# PLD_Sensors_AVR_Interface.net
KiCad netlist of a schematic drawn in Altium Designer
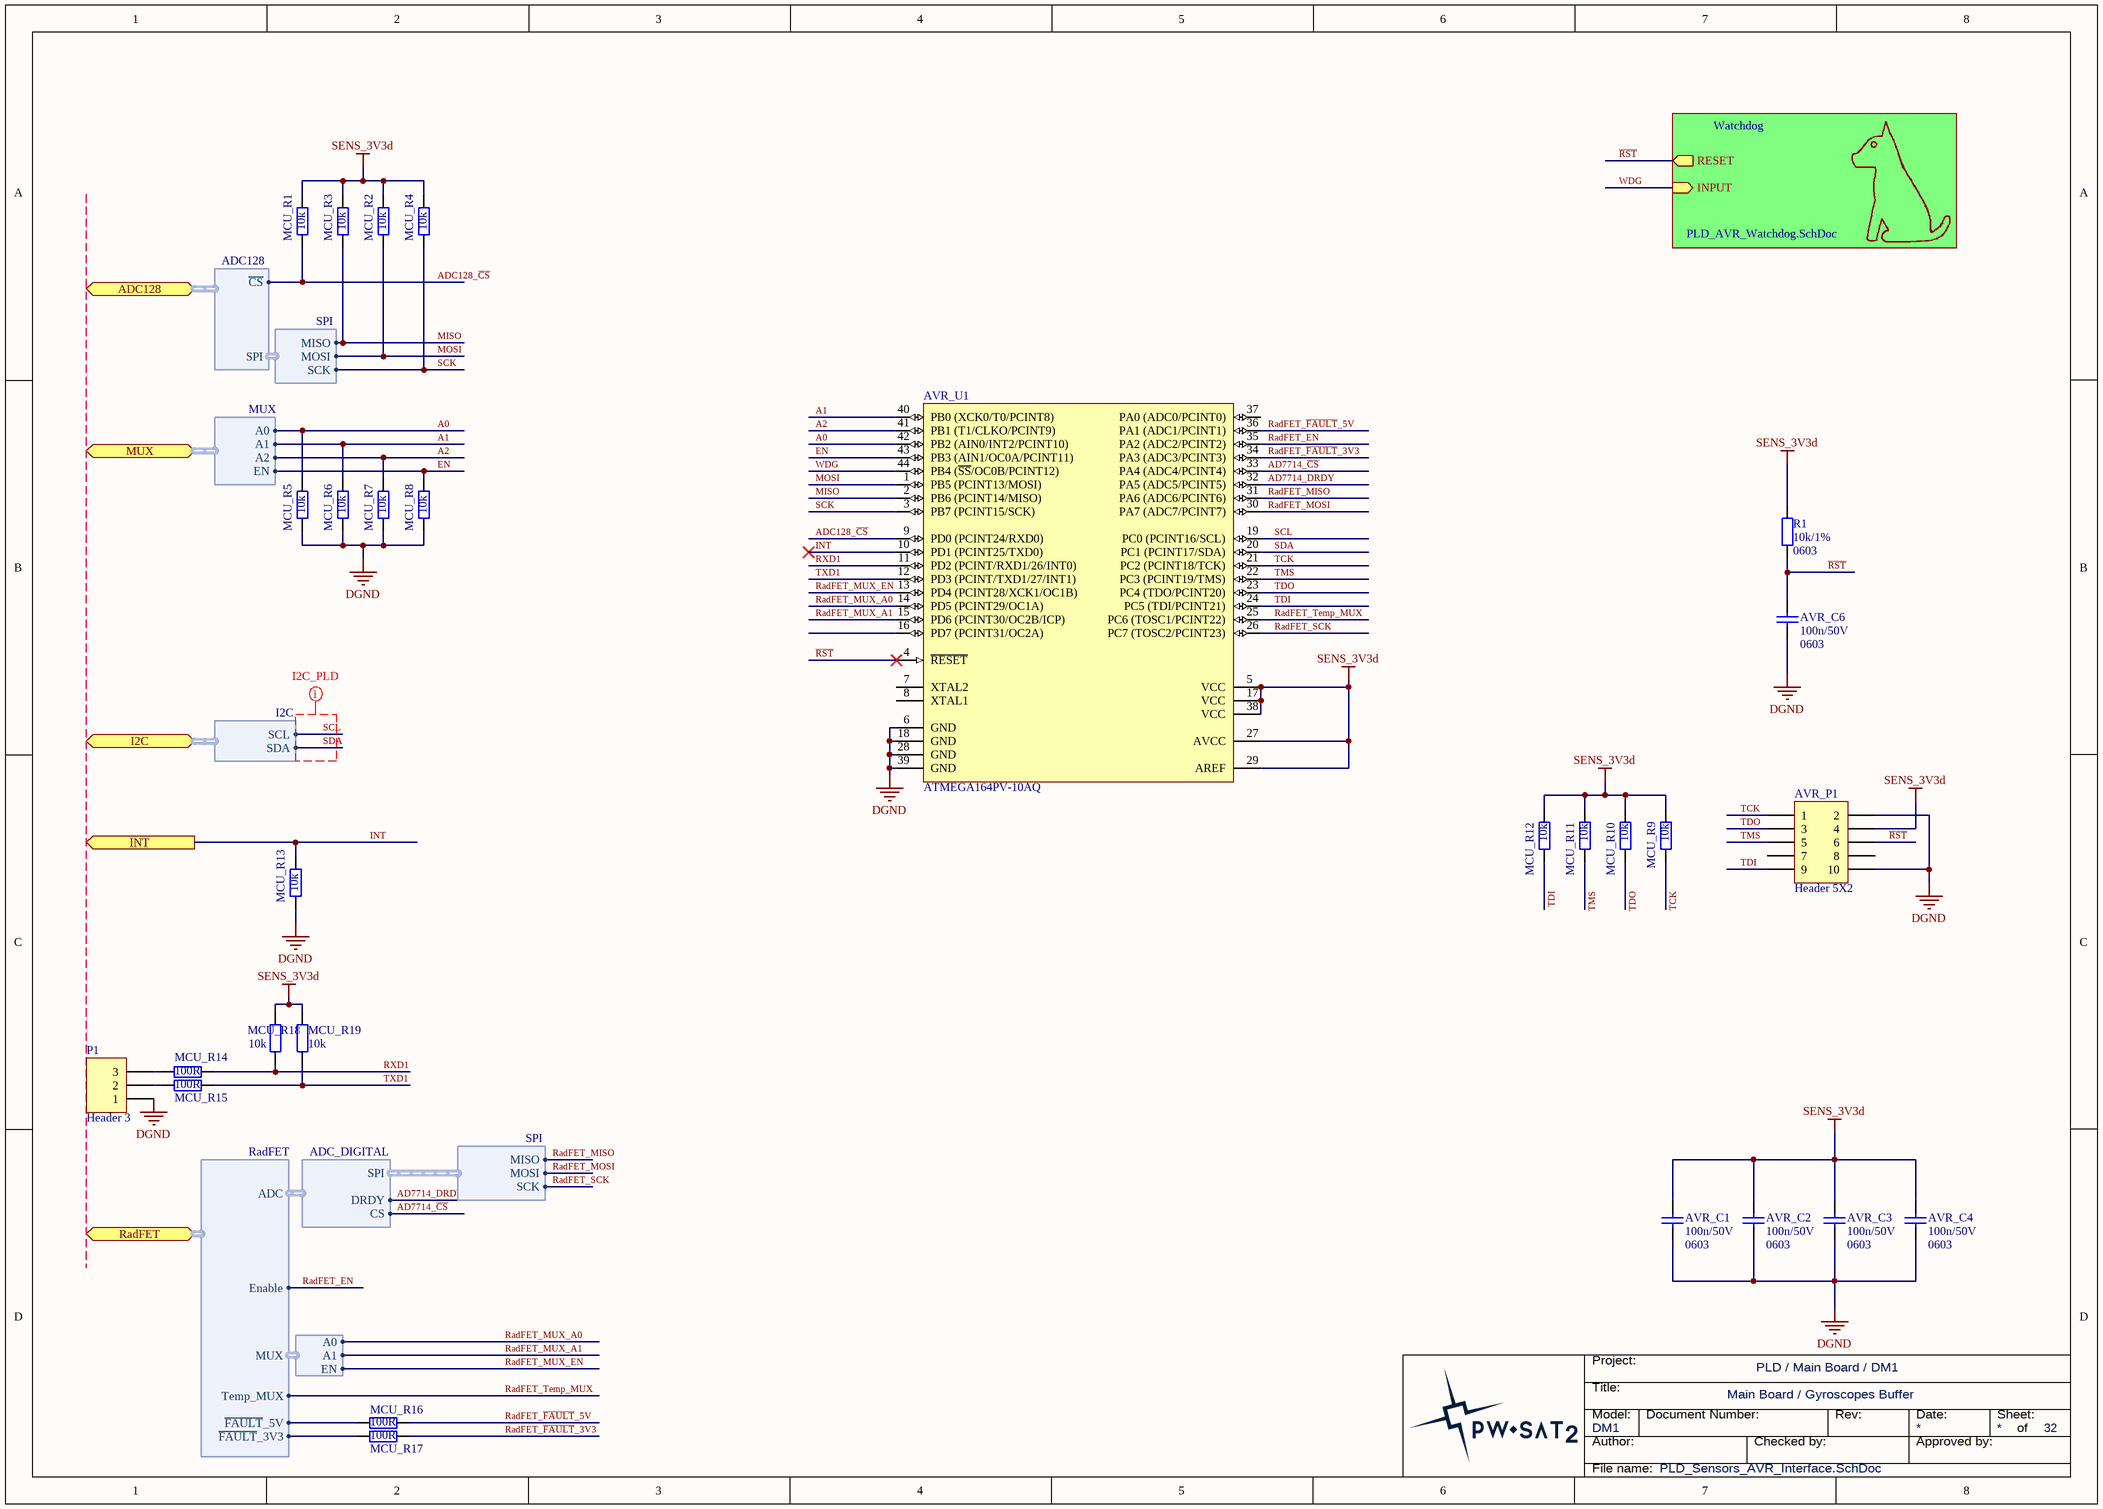
[diagram p0: PLD_Sensors_AVR_Interface.SchDoc]

(export (version "E")
  (design (tool "Eeschema 10.0.6"))
  (components
    (comp (ref "AVR_C1")
      (value "100n/50V")
      (footprint "SMD_Capacitor_0603")
      (description "Ceramic Cap Kemet COTS 100n/50V X7R 0603")
      (fields
        (field (name "MANUFACTURER") "Kemet")
        (field (name "MANUFACTURERPARTNUMBER") "C0603T104K5RALTU")
        (field (name "PACKAGE") "0603")
      )
      (libsource (lib "capacitors") (part "Cer_C0603T104K5RALTU"))
    )
    (comp (ref "AVR_C2")
      (value "100n/50V")
      (footprint "SMD_Capacitor_0603")
      (description "Ceramic Cap Kemet COTS 100n/50V X7R 0603")
      (fields
        (field (name "MANUFACTURER") "Kemet")
        (field (name "MANUFACTURERPARTNUMBER") "C0603T104K5RALTU")
        (field (name "PACKAGE") "0603")
      )
      (libsource (lib "capacitors") (part "Cer_C0603T104K5RALTU"))
    )
    (comp (ref "AVR_C3")
      (value "100n/50V")
      (footprint "SMD_Capacitor_0603")
      (description "Ceramic Cap Kemet COTS 100n/50V X7R 0603")
      (fields
        (field (name "MANUFACTURER") "Kemet")
        (field (name "MANUFACTURERPARTNUMBER") "C0603T104K5RALTU")
        (field (name "PACKAGE") "0603")
      )
      (libsource (lib "capacitors") (part "Cer_C0603T104K5RALTU"))
    )
    (comp (ref "AVR_C4")
      (value "100n/50V")
      (footprint "SMD_Capacitor_0603")
      (description "Ceramic Cap Kemet COTS 100n/50V X7R 0603")
      (fields
        (field (name "MANUFACTURER") "Kemet")
        (field (name "MANUFACTURERPARTNUMBER") "C0603T104K5RALTU")
        (field (name "PACKAGE") "0603")
      )
      (libsource (lib "capacitors") (part "Cer_C0603T104K5RALTU"))
    )
    (comp (ref "AVR_C6")
      (value "100n/50V")
      (footprint "SMD_Capacitor_0603")
      (description "Ceramic Cap Kemet COTS 100n/50V X7R 0603")
      (fields
        (field (name "MANUFACTURER") "Kemet")
        (field (name "MANUFACTURERPARTNUMBER") "C0603T104K5RALTU")
        (field (name "PACKAGE") "0603")
      )
      (libsource (lib "capacitors") (part "Cer_C0603T104K5RALTU"))
    )
    (comp (ref "AVR_P1")
      (value "Header 5X2")
      (footprint "HDR2X5")
      (description "Header, 5-Pin, Dual row")
      (fields (field (name "PUBLISHER") "Altium Limited"))
      (libsource (lib "Miscellaneous Connectors") (part "Header 5X2"))
    )
    (comp (ref "AVR_U1")
      (value "ATMEGA164PV-10AQ")
      (footprint "TQFP-44")
      (description "General-purpose microcontroller")
      (libsource (lib "microcircuits") (part "ATMEGA164PV-10AQ"))
    )
    (comp (ref "MCU_R1")
      (value "10k")
      (footprint "SMD_Resistor_0603")
      (libsource (lib "resistors") (part "Res"))
    )
    (comp (ref "MCU_R2")
      (value "10k")
      (footprint "SMD_Resistor_0603")
      (libsource (lib "resistors") (part "Res"))
    )
    (comp (ref "MCU_R3")
      (value "10k")
      (footprint "SMD_Resistor_0603")
      (libsource (lib "resistors") (part "Res"))
    )
    (comp (ref "MCU_R4")
      (value "10k")
      (footprint "SMD_Resistor_0603")
      (libsource (lib "resistors") (part "Res"))
    )
    (comp (ref "MCU_R5") (value "10k") (footprint "SMD_Resistor_0603") (libsource (lib "") (part "Res_1")))
    (comp (ref "MCU_R6") (value "10k") (footprint "SMD_Resistor_0603") (libsource (lib "") (part "Res_1")))
    (comp (ref "MCU_R7") (value "10k") (footprint "SMD_Resistor_0603") (libsource (lib "") (part "Res_1")))
    (comp (ref "MCU_R8") (value "10k") (footprint "SMD_Resistor_0603") (libsource (lib "") (part "Res_1")))
    (comp (ref "MCU_R9")
      (value "10k")
      (footprint "SMD_Resistor_0603")
      (libsource (lib "resistors") (part "Res"))
    )
    (comp (ref "MCU_R10")
      (value "10k")
      (footprint "SMD_Resistor_0603")
      (libsource (lib "resistors") (part "Res"))
    )
    (comp (ref "MCU_R11")
      (value "10k")
      (footprint "SMD_Resistor_0603")
      (libsource (lib "resistors") (part "Res"))
    )
    (comp (ref "MCU_R12")
      (value "10k")
      (footprint "SMD_Resistor_0603")
      (libsource (lib "resistors") (part "Res"))
    )
    (comp (ref "MCU_R13")
      (value "10k")
      (footprint "SMD_Resistor_0603")
      (libsource (lib "resistors") (part "Res"))
    )
    (comp (ref "MCU_R14") (value "100R") (footprint "SMD_Resistor_0603") (libsource (lib "") (part "Res_2")))
    (comp (ref "MCU_R15") (value "100R") (footprint "SMD_Resistor_0603") (libsource (lib "") (part "Res_2")))
    (comp (ref "MCU_R16") (value "100R") (footprint "SMD_Resistor_0603") (libsource (lib "") (part "Res_2")))
    (comp (ref "MCU_R17") (value "100R") (footprint "SMD_Resistor_0603") (libsource (lib "") (part "Res_2")))
    (comp (ref "MCU_R18")
      (value "10k")
      (footprint "SMD_Resistor_0603")
      (libsource (lib "resistors") (part "Res"))
    )
    (comp (ref "MCU_R19")
      (value "10k")
      (footprint "SMD_Resistor_0603")
      (libsource (lib "resistors") (part "Res"))
    )
    (comp (ref "P1")
      (value "Header 3")
      (footprint "HEADER1X3H Male")
      (description "Header, 3-Pin")
      (fields (field (name "PUBLISHER") "Altium Limited"))
      (libsource (lib "connectors_printed-circuit-board") (part "Header 3"))
    )
    (comp (ref "R1")
      (value "10k/1%")
      (footprint "SMD_Resistor_0603")
      (description "10k/1% Vishay CRCW 0603 Resistor. 100mW, 100ppm, 75V.")
      (fields
        (field (name "MANUFACTURER") "Vishay")
        (field (name "MANUFACTURERPARTNUMBER") "CRCW060310K0FKxxxx")
        (field (name "PACKAGE") "0603")
      )
      (libsource (lib "resistors") (part "CRCW060310K0FKxxxx"))
    )
  )
  (nets
    (net (code "8") (name "/A0") (class "Default")
      (node (ref "AVR_U1") (pin "42") (pinfunction "PB2_(AIN0/INT2/PCINT10)_42") (pintype "bidirectional"))
      (node (ref "MCU_R5") (pin "2") (pinfunction "2_2") (pintype "passive"))
    )
    (net (code "9") (name "/A1") (class "Default")
      (node (ref "AVR_U1") (pin "40") (pinfunction "PB0_(XCK0/T0/PCINT8)_40") (pintype "bidirectional"))
      (node (ref "MCU_R6") (pin "2") (pinfunction "2_2") (pintype "passive"))
    )
    (net (code "10") (name "/A2") (class "Default")
      (node (ref "AVR_U1") (pin "41") (pinfunction "PB1_(T1/CLKO/PCINT9)_41") (pintype "bidirectional"))
      (node (ref "MCU_R7") (pin "2") (pinfunction "2_2") (pintype "passive"))
    )
    (net (code "11") (name "/AD7714_DRDY") (class "Default")
      (node (ref "AVR_U1") (pin "32") (pinfunction "PA5_(ADC5/PCINT5)_32") (pintype "bidirectional"))
    )
    (net (code "12") (name "/AD7714_~{CS}") (class "Default")
      (node (ref "AVR_U1") (pin "33") (pinfunction "PA4_(ADC4/PCINT4)_33") (pintype "bidirectional"))
    )
    (net (code "13") (name "/ADC128_~{CS}") (class "Default")
      (node (ref "AVR_U1") (pin "9") (pinfunction "PD0_(PCINT24/RXD0)_9") (pintype "bidirectional"))
      (node (ref "MCU_R1") (pin "2") (pinfunction "2_2") (pintype "passive"))
    )
    (net (code "15") (name "/EN") (class "Default")
      (node (ref "AVR_U1") (pin "43") (pinfunction "PB3_(AIN1/OC0A/PCINT11)_43") (pintype "bidirectional"))
      (node (ref "MCU_R8") (pin "2") (pinfunction "2_2") (pintype "passive"))
    )
    (net (code "16") (name "/INT") (class "Default")
      (node (ref "AVR_U1") (pin "10") (pinfunction "PD1_(PCINT25/TXD0)_10") (pintype "bidirectional"))
      (node (ref "MCU_R13") (pin "1") (pinfunction "1_1") (pintype "passive"))
    )
    (net (code "17") (name "/MISO") (class "Default")
      (node (ref "AVR_U1") (pin "2") (pinfunction "PB6_(PCINT14/MISO)_2") (pintype "bidirectional"))
      (node (ref "MCU_R3") (pin "2") (pinfunction "2_2") (pintype "passive"))
    )
    (net (code "18") (name "/MOSI") (class "Default")
      (node (ref "AVR_U1") (pin "1") (pinfunction "PB5_(PCINT13/MOSI)_1") (pintype "bidirectional"))
      (node (ref "MCU_R2") (pin "2") (pinfunction "2_2") (pintype "passive"))
    )
    (net (code "19") (name "/RXD1") (class "Default")
      (node (ref "AVR_U1") (pin "11") (pinfunction "PD2_(PCINT/RXD1/26/INT0)_11") (pintype "bidirectional"))
      (node (ref "MCU_R14") (pin "1") (pinfunction "1_1") (pintype "passive"))
      (node (ref "MCU_R18") (pin "2") (pinfunction "2_2") (pintype "passive"))
    )
    (net (code "20") (name "/RadFET_EN") (class "Default")
      (node (ref "AVR_U1") (pin "35") (pinfunction "PA2_(ADC2/PCINT2)_35") (pintype "bidirectional"))
    )
    (net (code "21") (name "/RadFET_MISO") (class "Default")
      (node (ref "AVR_U1") (pin "31") (pinfunction "PA6_(ADC6/PCINT6)_31") (pintype "bidirectional"))
    )
    (net (code "22") (name "/RadFET_MOSI") (class "Default")
      (node (ref "AVR_U1") (pin "30") (pinfunction "PA7_(ADC7/PCINT7)_30") (pintype "bidirectional"))
    )
    (net (code "23") (name "/RadFET_MUX_A0") (class "Default")
      (node (ref "AVR_U1") (pin "14") (pinfunction "PD5_(PCINT29/OC1A)_14") (pintype "bidirectional"))
    )
    (net (code "24") (name "/RadFET_MUX_A1") (class "Default")
      (node (ref "AVR_U1") (pin "15") (pinfunction "PD6_(PCINT30/OC2B/ICP)_15") (pintype "bidirectional"))
    )
    (net (code "25") (name "/RadFET_MUX_EN") (class "Default")
      (node (ref "AVR_U1") (pin "13") (pinfunction "PD4_(PCINT28/XCK1/OC1B)_13") (pintype "bidirectional"))
    )
    (net (code "26") (name "/RadFET_SCK") (class "Default")
      (node (ref "AVR_U1") (pin "26") (pinfunction "PC7_(TOSC2/PCINT23)_26") (pintype "bidirectional"))
    )
    (net (code "27") (name "/RadFET_Temp_MUX") (class "Default")
      (node (ref "AVR_U1") (pin "25") (pinfunction "PC6_(TOSC1/PCINT22)_25") (pintype "bidirectional"))
    )
    (net (code "28") (name "/RadFET_~{FAULT}_3V3") (class "Default")
      (node (ref "AVR_U1") (pin "34") (pinfunction "PA3_(ADC3/PCINT3)_34") (pintype "bidirectional"))
      (node (ref "MCU_R17") (pin "1") (pinfunction "1_1") (pintype "passive"))
    )
    (net (code "29") (name "/RadFET_~{FAULT}_5V") (class "Default")
      (node (ref "AVR_U1") (pin "36") (pinfunction "PA1_(ADC1/PCINT1)_36") (pintype "bidirectional"))
      (node (ref "MCU_R16") (pin "1") (pinfunction "1_1") (pintype "passive"))
    )
    (net (code "30") (name "/SCK") (class "Default")
      (node (ref "AVR_U1") (pin "3") (pinfunction "PB7_(PCINT15/SCK)_3") (pintype "bidirectional"))
      (node (ref "MCU_R4") (pin "2") (pinfunction "2_2") (pintype "passive"))
    )
    (net (code "31") (name "/SCL") (class "Default")
      (node (ref "AVR_U1") (pin "19") (pinfunction "PC0_(PCINT16/SCL)_19") (pintype "bidirectional"))
    )
    (net (code "32") (name "/SDA") (class "Default")
      (node (ref "AVR_U1") (pin "20") (pinfunction "PC1_(PCINT17/SDA)_20") (pintype "bidirectional"))
    )
    (net (code "33") (name "/TCK") (class "Default")
      (node (ref "AVR_P1") (pin "1") (pinfunction "1_1") (pintype "passive"))
      (node (ref "AVR_U1") (pin "21") (pinfunction "PC2_(PCINT18/TCK)_21") (pintype "bidirectional"))
      (node (ref "MCU_R9") (pin "2") (pinfunction "2_2") (pintype "passive"))
    )
    (net (code "34") (name "/TDI") (class "Default")
      (node (ref "AVR_P1") (pin "9") (pinfunction "9_9") (pintype "passive"))
      (node (ref "AVR_U1") (pin "24") (pinfunction "PC5_(TDI/PCINT21)_24") (pintype "bidirectional"))
      (node (ref "MCU_R12") (pin "2") (pinfunction "2_2") (pintype "passive"))
    )
    (net (code "35") (name "/TDO") (class "Default")
      (node (ref "AVR_P1") (pin "3") (pinfunction "3_3") (pintype "passive"))
      (node (ref "AVR_U1") (pin "23") (pinfunction "PC4_(TDO/PCINT20)_23") (pintype "bidirectional"))
      (node (ref "MCU_R10") (pin "2") (pinfunction "2_2") (pintype "passive"))
    )
    (net (code "36") (name "/TMS") (class "Default")
      (node (ref "AVR_P1") (pin "5") (pinfunction "5_5") (pintype "passive"))
      (node (ref "AVR_U1") (pin "22") (pinfunction "PC3_(PCINT19/TMS)_22") (pintype "bidirectional"))
      (node (ref "MCU_R11") (pin "2") (pinfunction "2_2") (pintype "passive"))
    )
    (net (code "37") (name "/TXD1") (class "Default")
      (node (ref "AVR_U1") (pin "12") (pinfunction "PD3_(PCINT/TXD1/27/INT1)_12") (pintype "bidirectional"))
      (node (ref "MCU_R15") (pin "1") (pinfunction "1_1") (pintype "passive"))
      (node (ref "MCU_R19") (pin "2") (pinfunction "2_2") (pintype "passive"))
    )
    (net (code "38") (name "/WDG") (class "Default")
      (node (ref "AVR_U1") (pin "44") (pinfunction "PB4_(~{SS}/OC0B/PCINT12)_44") (pintype "bidirectional"))
    )
    (net (code "45") (name "/~{FAULT}_3V3") (class "Default")
      (node (ref "MCU_R17") (pin "2") (pinfunction "2_2") (pintype "passive"))
    )
    (net (code "46") (name "/~{FAULT}_5V") (class "Default")
      (node (ref "MCU_R16") (pin "2") (pinfunction "2_2") (pintype "passive"))
    )
    (net (code "47") (name "/~{RST}") (class "Default")
      (node (ref "AVR_C6") (pin "1") (pinfunction "1_1") (pintype "passive"))
      (node (ref "AVR_P1") (pin "6") (pinfunction "6_6") (pintype "passive"))
      (node (ref "AVR_U1") (pin "4") (pinfunction "~{RESET}_4") (pintype "input"))
      (node (ref "R1") (pin "2") (pinfunction "2_2") (pintype "passive"))
    )
    (net (code "48") (name "DGND") (class "Default")
      (node (ref "AVR_C1") (pin "2") (pinfunction "2_2") (pintype "passive"))
      (node (ref "AVR_C2") (pin "2") (pinfunction "2_2") (pintype "passive"))
      (node (ref "AVR_C3") (pin "2") (pinfunction "2_2") (pintype "passive"))
      (node (ref "AVR_C4") (pin "2") (pinfunction "2_2") (pintype "passive"))
      (node (ref "AVR_C6") (pin "2") (pinfunction "2_2") (pintype "passive"))
      (node (ref "AVR_P1") (pin "10") (pinfunction "10_10") (pintype "passive"))
      (node (ref "AVR_P1") (pin "2") (pinfunction "2_2") (pintype "passive"))
      (node (ref "AVR_U1") (pin "18") (pinfunction "GND_18") (pintype "power_in"))
      (node (ref "AVR_U1") (pin "28") (pinfunction "GND_28") (pintype "power_in"))
      (node (ref "AVR_U1") (pin "39") (pinfunction "GND_39") (pintype "power_in"))
      (node (ref "AVR_U1") (pin "6") (pinfunction "GND_6") (pintype "power_in"))
      (node (ref "MCU_R13") (pin "2") (pinfunction "2_2") (pintype "passive"))
      (node (ref "MCU_R5") (pin "1") (pinfunction "1_1") (pintype "passive"))
      (node (ref "MCU_R6") (pin "1") (pinfunction "1_1") (pintype "passive"))
      (node (ref "MCU_R7") (pin "1") (pinfunction "1_1") (pintype "passive"))
      (node (ref "MCU_R8") (pin "1") (pinfunction "1_1") (pintype "passive"))
      (node (ref "P1") (pin "1") (pinfunction "1_1") (pintype "passive"))
    )
    (net (code "49") (name "Net-(MCU_R14-Pad2)") (class "Default")
      (node (ref "MCU_R14") (pin "2") (pinfunction "2_2") (pintype "passive"))
      (node (ref "P1") (pin "3") (pinfunction "3_3") (pintype "passive"))
    )
    (net (code "50") (name "Net-(MCU_R15-Pad2)") (class "Default")
      (node (ref "MCU_R15") (pin "2") (pinfunction "2_2") (pintype "passive"))
      (node (ref "P1") (pin "2") (pinfunction "2_2") (pintype "passive"))
    )
    (net (code "51") (name "SENS_3V3d") (class "Default")
      (node (ref "AVR_C1") (pin "1") (pinfunction "1_1") (pintype "passive"))
      (node (ref "AVR_C2") (pin "1") (pinfunction "1_1") (pintype "passive"))
      (node (ref "AVR_C3") (pin "1") (pinfunction "1_1") (pintype "passive"))
      (node (ref "AVR_C4") (pin "1") (pinfunction "1_1") (pintype "passive"))
      (node (ref "AVR_P1") (pin "4") (pinfunction "4_4") (pintype "passive"))
      (node (ref "AVR_U1") (pin "17") (pinfunction "VCC_17") (pintype "power_in"))
      (node (ref "AVR_U1") (pin "27") (pinfunction "AVCC_27") (pintype "power_in"))
      (node (ref "AVR_U1") (pin "29") (pinfunction "AREF_29") (pintype "power_in"))
      (node (ref "AVR_U1") (pin "38") (pinfunction "VCC_38") (pintype "power_in"))
      (node (ref "AVR_U1") (pin "5") (pinfunction "VCC_5") (pintype "power_in"))
      (node (ref "MCU_R1") (pin "1") (pinfunction "1_1") (pintype "passive"))
      (node (ref "MCU_R10") (pin "1") (pinfunction "1_1") (pintype "passive"))
      (node (ref "MCU_R11") (pin "1") (pinfunction "1_1") (pintype "passive"))
      (node (ref "MCU_R12") (pin "1") (pinfunction "1_1") (pintype "passive"))
      (node (ref "MCU_R18") (pin "1") (pinfunction "1_1") (pintype "passive"))
      (node (ref "MCU_R19") (pin "1") (pinfunction "1_1") (pintype "passive"))
      (node (ref "MCU_R2") (pin "1") (pinfunction "1_1") (pintype "passive"))
      (node (ref "MCU_R3") (pin "1") (pinfunction "1_1") (pintype "passive"))
      (node (ref "MCU_R4") (pin "1") (pinfunction "1_1") (pintype "passive"))
      (node (ref "MCU_R9") (pin "1") (pinfunction "1_1") (pintype "passive"))
      (node (ref "R1") (pin "1") (pinfunction "1_1") (pintype "passive"))
    )
    (net (code "52") (name "unconnected-(AVR_P1-Pad7)") (class "Default")
      (node (ref "AVR_P1") (pin "7") (pinfunction "7_7") (pintype "passive"))
    )
    (net (code "53") (name "unconnected-(AVR_P1-Pad8)") (class "Default")
      (node (ref "AVR_P1") (pin "8") (pinfunction "8_8") (pintype "passive"))
    )
    (net (code "54") (name "unconnected-(AVR_U1-PA0_(ADC0{slash}PCINT0)-Pad37)") (class "Default")
      (node (ref "AVR_U1") (pin "37") (pinfunction "PA0_(ADC0/PCINT0)_37") (pintype "bidirectional"))
    )
    (net (code "55") (name "unconnected-(AVR_U1-PD7_(PCINT31{slash}OC2A)-Pad16)") (class "Default")
      (node (ref "AVR_U1") (pin "16") (pinfunction "PD7_(PCINT31/OC2A)_16") (pintype "bidirectional"))
    )
    (net (code "56") (name "unconnected-(AVR_U1-XTAL1-Pad8)") (class "Default")
      (node (ref "AVR_U1") (pin "8") (pinfunction "XTAL1_8") (pintype "passive"))
    )
    (net (code "57") (name "unconnected-(AVR_U1-XTAL2-Pad7)") (class "Default")
      (node (ref "AVR_U1") (pin "7") (pinfunction "XTAL2_7") (pintype "passive"))
    )
  )
)
